# ST_LINK_V2-1.net
KiCad netlist of a schematic drawn in Altium Designer
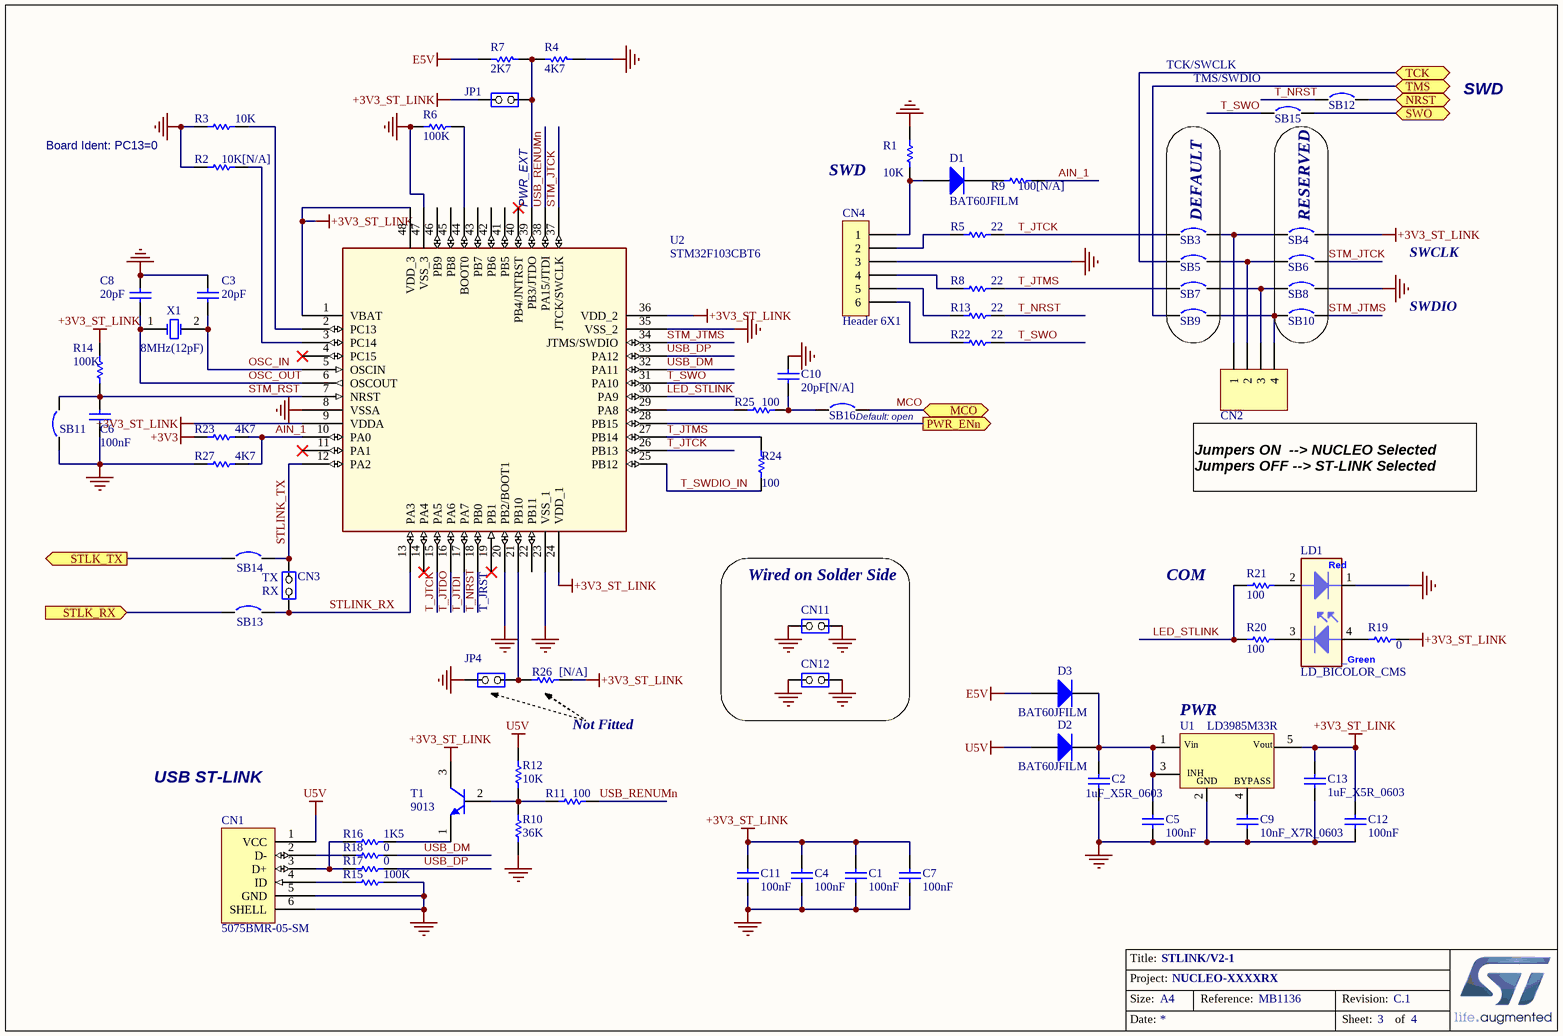
[diagram p0: ST_LINK_V2-1.SCHDOC]

(export (version "E")
  (design (tool "Eeschema 10.0.6"))
  (components
    (comp (ref "C1")
      (value "100nF")
      (footprint "0603C")
      (description "Capacitor 0402 / 0603 / 0805")
      (libsource (lib "MCD_TOOLS") (part "Capacitor_ST"))
    )
    (comp (ref "C2")
      (value "1uF_X5R_0603")
      (footprint "0603C")
      (description "0603  X5R 1µF")
      (fields (field (name "TOLERANCE") "10%"))
      (libsource (lib "MB963_1") (part "CAP SMD 0603  X5R 1µF 25V 10%"))
    )
    (comp (ref "C3")
      (value "20pF")
      (footprint "0603C")
      (description "Capacitor 0402 / 0603 / 0805")
      (libsource (lib "MCD_TOOLS") (part "Capacitor_ST"))
    )
    (comp (ref "C4")
      (value "100nF")
      (footprint "0603C")
      (description "Capacitor 0402 / 0603 / 0805")
      (libsource (lib "MCD_TOOLS") (part "Capacitor_ST"))
    )
    (comp (ref "C5")
      (value "100nF")
      (footprint "0603C")
      (description "Capacitor 0402 / 0603 / 0805")
      (libsource (lib "MCD_TOOLS") (part "Capacitor_ST"))
    )
    (comp (ref "C6")
      (value "100nF")
      (footprint "0603C")
      (description "Capacitor 0402 / 0603 / 0805")
      (libsource (lib "MCD_TOOLS") (part "Capacitor_ST"))
    )
    (comp (ref "C7")
      (value "100nF")
      (footprint "0603C")
      (description "Capacitor 0402 / 0603 / 0805")
      (libsource (lib "MCD_TOOLS") (part "Capacitor_ST"))
    )
    (comp (ref "C8")
      (value "20pF")
      (footprint "0603C")
      (description "Capacitor 0402 / 0603 / 0805")
      (libsource (lib "MCD_TOOLS") (part "Capacitor_ST"))
    )
    (comp (ref "C9")
      (value "10nF_X7R_0603")
      (footprint "0603C")
      (description "0603  X7R 10NF")
      (fields (field (name "TOLERANCE") "10%"))
      (libsource (lib "MB963_1") (part "CAP SMD 0603  X7R 10000PF 50V 10%"))
    )
    (comp (ref "C10")
      (value "20pF[N/A]")
      (footprint "0603C")
      (description "Capacitor 0402 / 0603 / 0805")
      (libsource (lib "MCD_TOOLS") (part "Capacitor_ST"))
    )
    (comp (ref "C11")
      (value "100nF")
      (footprint "0603C")
      (description "Capacitor 0402 / 0603 / 0805")
      (libsource (lib "MCD_TOOLS") (part "Capacitor_ST"))
    )
    (comp (ref "C12")
      (value "100nF")
      (footprint "0603C")
      (description "Capacitor 0402 / 0603 / 0805")
      (libsource (lib "MCD_TOOLS") (part "Capacitor_ST"))
    )
    (comp (ref "C13")
      (value "1uF_X5R_0603")
      (footprint "0603C")
      (description "0603  X5R 1µF")
      (fields (field (name "TOLERANCE") "10%"))
      (libsource (lib "MB963_1") (part "CAP SMD 0603  X5R 1µF 25V 10%"))
    )
    (comp (ref "CN1")
      (value "5075BMR-05-SM")
      (footprint "USB-MINI-B-SMD")
      (description "USB-MINI-typeB connector")
      (libsource (lib "MCD_TOOLS") (part "USB-MINI-typeB connector"))
    )
    (comp (ref "CN2")
      (value "Header 4")
      (footprint "1*4")
      (description "Header, 4-Pin, Single row")
      (fields (field (name "PUBLISHER") "Altium Limited"))
      (libsource (lib "Nucleo_64") (part "Header 4"))
    )
    (comp (ref "CN3") (value "~") (footprint "SIP2/2.54") (libsource (lib "MCD_TOOLS") (part "JP2")))
    (comp (ref "CN4")
      (value "Header 6X1")
      (footprint "1*6P")
      (description "Header, 6-Pin, Single row")
      (fields (field (name "PUBLISHER") "Altium Limited"))
      (libsource (lib "Nucleo_64") (part "Header 6X1"))
    )
    (comp (ref "CN11") (value "~") (footprint "SIP2/2.54") (libsource (lib "*") (part "JP2")))
    (comp (ref "CN12") (value "~") (footprint "SIP2/2.54") (libsource (lib "*") (part "JP2")))
    (comp (ref "D1")
      (value "BAT60JFILM")
      (footprint "SOD323/A")
      (libsource (lib "MCD_TOOLS") (part "BAT60JFILM"))
    )
    (comp (ref "D2")
      (value "BAT60JFILM")
      (footprint "SOD323/A")
      (libsource (lib "MCD_TOOLS") (part "BAT60JFILM"))
    )
    (comp (ref "D3")
      (value "BAT60JFILM")
      (footprint "SOD323/A")
      (libsource (lib "MCD_TOOLS") (part "BAT60JFILM"))
    )
    (comp (ref "JP1") (value "~") (footprint "SIP2/2.54") (libsource (lib "*") (part "JP2")))
    (comp (ref "JP4") (value "~") (footprint "SIP2/2.54") (libsource (lib "*") (part "JP2")))
    (comp (ref "LD1")
      (value "LD_BICOLOR_CMS")
      (footprint "HSMF-A201")
      (description "Bicolor Led")
      (libsource (lib "MCD_TOOLS") (part "LD_BICOLOR_CMS"))
    )
    (comp (ref "R1")
      (value "10K")
      (footprint "0603R")
      (description "Resistor 0402 or 0603 or 0805")
      (libsource (lib "Miscellaneous Devices") (part "Res1"))
    )
    (comp (ref "R2")
      (value "10K[N/A]")
      (footprint "0603R")
      (description "Resistor 0402 or 0603 or 0805")
      (libsource (lib "Miscellaneous Devices") (part "Res1"))
    )
    (comp (ref "R3")
      (value "10K")
      (footprint "0603R")
      (description "Resistor 0402 or 0603 or 0805")
      (libsource (lib "Miscellaneous Devices") (part "Res1"))
    )
    (comp (ref "R4")
      (value "4K7")
      (footprint "0603R")
      (description "Resistor")
      (fields (field (name "PUBLISHER") "Altium Limited"))
      (libsource (lib "") (part "Res1_1"))
    )
    (comp (ref "R5")
      (value "22")
      (footprint "0603R")
      (description "Resistor 0402 or 0603 or 0805")
      (libsource (lib "Miscellaneous Devices") (part "Res1"))
    )
    (comp (ref "R6")
      (value "100K")
      (footprint "0603R")
      (description "Resistor 0402 or 0603 or 0805")
      (libsource (lib "Miscellaneous Devices") (part "Res1"))
    )
    (comp (ref "R7")
      (value "2K7")
      (footprint "0603R")
      (description "Resistor")
      (fields (field (name "PUBLISHER") "Altium Limited"))
      (libsource (lib "") (part "Res1_1"))
    )
    (comp (ref "R8")
      (value "22")
      (footprint "0603R")
      (description "Resistor 0402 or 0603 or 0805")
      (libsource (lib "Miscellaneous Devices") (part "Res1"))
    )
    (comp (ref "R9")
      (value "100[N/A]")
      (footprint "0603R")
      (description "Resistor 0402 or 0603 or 0805")
      (libsource (lib "Miscellaneous Devices") (part "Res1"))
    )
    (comp (ref "R10")
      (value "36K")
      (footprint "0603R")
      (description "Resistor")
      (fields (field (name "PUBLISHER") "Altium Limited"))
      (libsource (lib "") (part "Res1_2"))
    )
    (comp (ref "R11")
      (value "100")
      (footprint "0603R")
      (description "Resistor 0402 or 0603 or 0805")
      (libsource (lib "Miscellaneous Devices") (part "Res1"))
    )
    (comp (ref "R12")
      (value "10K")
      (footprint "0603R")
      (description "Resistor")
      (fields (field (name "PUBLISHER") "Altium Limited"))
      (libsource (lib "") (part "Res1_2"))
    )
    (comp (ref "R13")
      (value "22")
      (footprint "0603R")
      (description "Resistor 0402 or 0603 or 0805")
      (libsource (lib "Miscellaneous Devices") (part "Res1"))
    )
    (comp (ref "R14")
      (value "100K")
      (footprint "0603R")
      (description "Resistor 0402 or 0603 or 0805")
      (libsource (lib "Miscellaneous Devices") (part "Res1"))
    )
    (comp (ref "R15")
      (value "100K")
      (footprint "0603R")
      (description "Resistor 0402 or 0603 or 0805")
      (libsource (lib "Miscellaneous Devices") (part "Res1"))
    )
    (comp (ref "R16")
      (value "1K5")
      (footprint "0603R")
      (description "Resistor 0402 or 0603 or 0805")
      (libsource (lib "Miscellaneous Devices") (part "Res1"))
    )
    (comp (ref "R17")
      (value "0")
      (footprint "0603R")
      (description "Resistor 0402 or 0603 or 0805")
      (libsource (lib "Miscellaneous Devices") (part "Res1"))
    )
    (comp (ref "R18")
      (value "0")
      (footprint "0603R")
      (description "Resistor 0402 or 0603 or 0805")
      (libsource (lib "Miscellaneous Devices") (part "Res1"))
    )
    (comp (ref "R19")
      (value "0")
      (footprint "0603R")
      (description "Resistor 0402 or 0603 or 0805")
      (libsource (lib "Miscellaneous Devices") (part "Res1"))
    )
    (comp (ref "R20")
      (value "100")
      (footprint "0603R")
      (description "Resistor 0402 or 0603 or 0805")
      (libsource (lib "Miscellaneous Devices") (part "Res1"))
    )
    (comp (ref "R21")
      (value "100")
      (footprint "0603R")
      (description "Resistor 0402 or 0603 or 0805")
      (libsource (lib "Miscellaneous Devices") (part "Res1"))
    )
    (comp (ref "R22")
      (value "22")
      (footprint "0603R")
      (description "Resistor 0402 or 0603 or 0805")
      (libsource (lib "Miscellaneous Devices") (part "Res1"))
    )
    (comp (ref "R23")
      (value "4K7")
      (footprint "0603R")
      (description "Resistor 0402 or 0603 or 0805")
      (libsource (lib "Miscellaneous Devices") (part "Res1"))
    )
    (comp (ref "R24")
      (value "100")
      (footprint "0603R")
      (description "Resistor 0402 or 0603 or 0805")
      (libsource (lib "Miscellaneous Devices") (part "Res1"))
    )
    (comp (ref "R25")
      (value "100")
      (footprint "0603R")
      (description "Resistor 0402 or 0603 or 0805")
      (libsource (lib "Miscellaneous Devices") (part "Res1"))
    )
    (comp (ref "R26")
      (value "[N/A]")
      (footprint "0603R")
      (description "Resistor")
      (fields (field (name "PUBLISHER") "Altium Limited"))
      (libsource (lib "") (part "Res1_2"))
    )
    (comp (ref "R27")
      (value "4K7")
      (footprint "0603R")
      (description "Resistor 0402 or 0603 or 0805")
      (libsource (lib "Miscellaneous Devices") (part "Res1"))
    )
    (comp (ref "SB3")
      (value "Circuit Breaker")
      (footprint "JP2_SMD")
      (fields (field (name "PUBLISHER") "Altium Limited"))
      (libsource (lib "MB915") (part "Circuit Breaker"))
    )
    (comp (ref "SB4")
      (value "Circuit Breaker")
      (footprint "JP2_SMD")
      (fields (field (name "PUBLISHER") "Altium Limited"))
      (libsource (lib "MB915") (part "Circuit Breaker"))
    )
    (comp (ref "SB5")
      (value "Circuit Breaker")
      (footprint "JP2_SMD")
      (fields (field (name "PUBLISHER") "Altium Limited"))
      (libsource (lib "MB915") (part "Circuit Breaker"))
    )
    (comp (ref "SB6")
      (value "Circuit Breaker")
      (footprint "JP2_SMD")
      (fields (field (name "PUBLISHER") "Altium Limited"))
      (libsource (lib "MB915") (part "Circuit Breaker"))
    )
    (comp (ref "SB7")
      (value "Circuit Breaker")
      (footprint "JP2_SMD")
      (fields (field (name "PUBLISHER") "Altium Limited"))
      (libsource (lib "MB915") (part "Circuit Breaker"))
    )
    (comp (ref "SB8")
      (value "Circuit Breaker")
      (footprint "JP2_SMD")
      (fields (field (name "PUBLISHER") "Altium Limited"))
      (libsource (lib "MB915") (part "Circuit Breaker"))
    )
    (comp (ref "SB9")
      (value "Circuit Breaker")
      (footprint "JP2_SMD")
      (fields (field (name "PUBLISHER") "Altium Limited"))
      (libsource (lib "MB915") (part "Circuit Breaker"))
    )
    (comp (ref "SB10")
      (value "Circuit Breaker")
      (footprint "JP2_SMD")
      (fields (field (name "PUBLISHER") "Altium Limited"))
      (libsource (lib "MB915") (part "Circuit Breaker"))
    )
    (comp (ref "SB11")
      (value "Circuit Breaker")
      (footprint "JP2_SMD")
      (fields (field (name "PUBLISHER") "Altium Limited"))
      (libsource (lib "MB915") (part "Circuit Breaker"))
    )
    (comp (ref "SB12")
      (value "Circuit Breaker")
      (footprint "JP2_SMD")
      (fields (field (name "PUBLISHER") "Altium Limited"))
      (libsource (lib "MB915") (part "Circuit Breaker"))
    )
    (comp (ref "SB13")
      (value "Circuit Breaker")
      (footprint "JP2_SMD")
      (fields (field (name "PUBLISHER") "Altium Limited"))
      (libsource (lib "MCD_TOOLS") (part "Circuit Breaker"))
    )
    (comp (ref "SB14")
      (value "Circuit Breaker")
      (footprint "JP2_SMD")
      (fields (field (name "PUBLISHER") "Altium Limited"))
      (libsource (lib "MCD_TOOLS") (part "Circuit Breaker"))
    )
    (comp (ref "SB15")
      (value "Circuit Breaker")
      (footprint "JP2_SMD")
      (fields (field (name "PUBLISHER") "Altium Limited"))
      (libsource (lib "MCD_TOOLS") (part "Circuit Breaker"))
    )
    (comp (ref "SB16")
      (value "Circuit Breaker")
      (footprint "JP2_SMD")
      (fields (field (name "PUBLISHER") "Altium Limited"))
      (libsource (lib "MCD_TOOLS") (part "Circuit Breaker"))
    )
    (comp (ref "T1")
      (value "9013")
      (footprint "SOT-23")
      (description "NPN Bipolar Transistor")
      (fields (field (name "PUBLISHER") "Altium Limited"))
      (libsource (lib "Miscellaneous Devices") (part "NPN"))
    )
    (comp (ref "U1")
      (value "LD3985M33R")
      (footprint "SOT-23-5L")
      (description "Ultra low drop-low noise BiCMOS voltage, regulators low ESR capacitors compatible")
      (libsource (lib "MCD_TOOLS") (part "LD3985M33R"))
    )
    (comp (ref "U2")
      (value "STM32F103CBT6")
      (footprint "QFP48 7X7")
      (description "Medium-density performance line ARM-based 32-bit MCU with 64KB Flash")
      (libsource (lib "Nucleo_64") (part "STM32F103CBT6"))
    )
    (comp (ref "X1")
      (value "8MHz(12pF)")
      (footprint "XTAL1")
      (description "Crystal Oscillator")
      (fields (field (name "PUBLISHER") "Altium Limited"))
      (libsource (lib "MB963_1") (part "XTAL"))
    )
  )
  (nets
    (net (code "1") (name "+3V3") (class "Default")
      (node (ref "R23") (pin "1") (pinfunction "1_1") (pintype "passive"))
    )
    (net (code "2") (name "+3V3_ST_LINK") (class "Default")
      (node (ref "C1") (pin "2") (pinfunction "2_2") (pintype "passive"))
      (node (ref "C11") (pin "2") (pinfunction "2_2") (pintype "passive"))
      (node (ref "C12") (pin "2") (pinfunction "2_2") (pintype "passive"))
      (node (ref "C13") (pin "1") (pinfunction "1_1") (pintype "passive"))
      (node (ref "C4") (pin "2") (pinfunction "2_2") (pintype "passive"))
      (node (ref "C7") (pin "2") (pinfunction "2_2") (pintype "passive"))
      (node (ref "JP1") (pin "1") (pinfunction "COMMON_1") (pintype "passive"))
      (node (ref "R14") (pin "2") (pinfunction "2_2") (pintype "passive"))
      (node (ref "R19") (pin "2") (pinfunction "2_2") (pintype "passive"))
      (node (ref "R26") (pin "1") (pinfunction "1_1") (pintype "passive"))
      (node (ref "SB4") (pin "2") (pinfunction "2_2") (pintype "passive"))
      (node (ref "T1") (pin "3") (pinfunction "C_3") (pintype "passive"))
      (node (ref "U1") (pin "5") (pinfunction "Vout_5") (pintype "passive"))
      (node (ref "U2") (pin "1") (pinfunction "VBAT_1") (pintype "power_in"))
      (node (ref "U2") (pin "24") (pinfunction "VDD_1_24") (pintype "power_in"))
      (node (ref "U2") (pin "36") (pinfunction "VDD_2_36") (pintype "power_in"))
      (node (ref "U2") (pin "48") (pinfunction "VDD_3_48") (pintype "power_in"))
      (node (ref "U2") (pin "9") (pinfunction "VDDA_9") (pintype "power_in"))
    )
    (net (code "3") (name "/AIN_1") (class "Default")
      (node (ref "R23") (pin "2") (pinfunction "2_2") (pintype "passive"))
      (node (ref "R27") (pin "2") (pinfunction "2_2") (pintype "passive"))
      (node (ref "R9") (pin "2") (pinfunction "2_2") (pintype "passive"))
      (node (ref "U2") (pin "10") (pinfunction "PA0_10") (pintype "bidirectional"))
    )
    (net (code "4") (name "/LED_STLINK") (class "Default")
      (node (ref "R20") (pin "1") (pinfunction "1_1") (pintype "passive"))
      (node (ref "R21") (pin "1") (pinfunction "1_1") (pintype "passive"))
      (node (ref "U2") (pin "30") (pinfunction "PA9_30") (pintype "bidirectional"))
    )
    (net (code "5") (name "/MCO") (class "Default")
      (node (ref "SB16") (pin "2") (pinfunction "2_2") (pintype "passive"))
    )
    (net (code "6") (name "/NRST") (class "Default")
      (node (ref "SB12") (pin "2") (pinfunction "2_2") (pintype "passive"))
    )
    (net (code "7") (name "/OSC_IN") (class "Default")
      (node (ref "C3") (pin "1") (pinfunction "1_1") (pintype "passive"))
      (node (ref "U2") (pin "5") (pinfunction "OSCIN_5") (pintype "input"))
      (node (ref "X1") (pin "2") (pinfunction "OSC2_2") (pintype "passive"))
    )
    (net (code "8") (name "/OSC_OUT") (class "Default")
      (node (ref "C8") (pin "1") (pinfunction "1_1") (pintype "passive"))
      (node (ref "U2") (pin "6") (pinfunction "OSCOUT_6") (pintype "output"))
      (node (ref "X1") (pin "1") (pinfunction "OSC1_1") (pintype "passive"))
    )
    (net (code "9") (name "/PWR_ENn") (class "Default")
      (node (ref "U2") (pin "28") (pinfunction "PB15_28") (pintype "bidirectional"))
    )
    (net (code "10") (name "/STLINK_RX") (class "Default")
      (node (ref "CN3") (pin "1") (pinfunction "COMMON_1") (pintype "passive"))
      (node (ref "SB13") (pin "2") (pinfunction "2_2") (pintype "passive"))
      (node (ref "U2") (pin "13") (pinfunction "PA3_13") (pintype "bidirectional"))
    )
    (net (code "11") (name "/STLINK_TX") (class "Default")
      (node (ref "CN3") (pin "2") (pinfunction "NO_2") (pintype "passive"))
      (node (ref "SB14") (pin "2") (pinfunction "2_2") (pintype "passive"))
      (node (ref "U2") (pin "12") (pinfunction "PA2_12") (pintype "bidirectional"))
    )
    (net (code "12") (name "/STLK_RX") (class "Default")
      (node (ref "SB13") (pin "1") (pinfunction "1_1") (pintype "passive"))
    )
    (net (code "13") (name "/STLK_TX") (class "Default")
      (node (ref "SB14") (pin "1") (pinfunction "1_1") (pintype "passive"))
    )
    (net (code "14") (name "/STM_JTCK") (class "Default")
      (node (ref "SB6") (pin "2") (pinfunction "2_2") (pintype "passive"))
      (node (ref "U2") (pin "37") (pinfunction "JTCK/SWCLK_37") (pintype "bidirectional"))
    )
    (net (code "15") (name "/STM_JTMS") (class "Default")
      (node (ref "SB10") (pin "2") (pinfunction "2_2") (pintype "passive"))
      (node (ref "U2") (pin "34") (pinfunction "JTMS/SWDIO_34") (pintype "bidirectional"))
    )
    (net (code "16") (name "/STM_RST") (class "Default")
      (node (ref "C6") (pin "2") (pinfunction "2_2") (pintype "passive"))
      (node (ref "R14") (pin "1") (pinfunction "1_1") (pintype "passive"))
      (node (ref "SB11") (pin "2") (pinfunction "2_2") (pintype "passive"))
      (node (ref "U2") (pin "7") (pinfunction "NRST_7") (pintype "input"))
    )
    (net (code "17") (name "/SWO") (class "Default")
      (node (ref "SB15") (pin "2") (pinfunction "2_2") (pintype "passive"))
    )
    (net (code "18") (name "/TCK") (class "Default")
      (node (ref "SB5") (pin "1") (pinfunction "1_1") (pintype "passive"))
    )
    (net (code "19") (name "/TMS") (class "Default")
      (node (ref "SB9") (pin "1") (pinfunction "1_1") (pintype "passive"))
    )
    (net (code "20") (name "/T_JTCK") (class "Default")
      (node (ref "R5") (pin "2") (pinfunction "2_2") (pintype "passive"))
      (node (ref "SB3") (pin "1") (pinfunction "1_1") (pintype "passive"))
      (node (ref "U2") (pin "15") (pinfunction "PA5_15") (pintype "bidirectional"))
      (node (ref "U2") (pin "26") (pinfunction "PB13_26") (pintype "bidirectional"))
    )
    (net (code "21") (name "/T_JTDI") (class "Default")
      (node (ref "U2") (pin "17") (pinfunction "PA7_17") (pintype "bidirectional"))
    )
    (net (code "22") (name "/T_JTDO") (class "Default")
      (node (ref "U2") (pin "16") (pinfunction "PA6_16") (pintype "bidirectional"))
    )
    (net (code "23") (name "/T_JTMS") (class "Default")
      (node (ref "R24") (pin "2") (pinfunction "2_2") (pintype "passive"))
      (node (ref "R8") (pin "2") (pinfunction "2_2") (pintype "passive"))
      (node (ref "SB7") (pin "1") (pinfunction "1_1") (pintype "passive"))
      (node (ref "U2") (pin "27") (pinfunction "PB14_27") (pintype "bidirectional"))
    )
    (net (code "24") (name "/T_NRST") (class "Default")
      (node (ref "R13") (pin "2") (pinfunction "2_2") (pintype "passive"))
      (node (ref "SB12") (pin "1") (pinfunction "1_1") (pintype "passive"))
      (node (ref "U2") (pin "18") (pinfunction "PB0_18") (pintype "bidirectional"))
    )
    (net (code "25") (name "/T_SWDIO_IN") (class "Default")
      (node (ref "R24") (pin "1") (pinfunction "1_1") (pintype "passive"))
      (node (ref "U2") (pin "25") (pinfunction "PB12_25") (pintype "bidirectional"))
    )
    (net (code "26") (name "/T_SWO") (class "Default")
      (node (ref "R22") (pin "2") (pinfunction "2_2") (pintype "passive"))
      (node (ref "SB15") (pin "1") (pinfunction "1_1") (pintype "passive"))
      (node (ref "U2") (pin "31") (pinfunction "PA10_31") (pintype "bidirectional"))
    )
    (net (code "27") (name "/USB_DM") (class "Default")
      (node (ref "R18") (pin "2") (pinfunction "2_2") (pintype "passive"))
      (node (ref "U2") (pin "32") (pinfunction "PA11_32") (pintype "bidirectional"))
    )
    (net (code "28") (name "/USB_DP") (class "Default")
      (node (ref "R17") (pin "2") (pinfunction "2_2") (pintype "passive"))
      (node (ref "U2") (pin "33") (pinfunction "PA12_33") (pintype "bidirectional"))
    )
    (net (code "29") (name "/USB_RENUMn") (class "Default")
      (node (ref "R11") (pin "2") (pinfunction "2_2") (pintype "passive"))
      (node (ref "U2") (pin "38") (pinfunction "PA15/JTDI_38") (pintype "bidirectional"))
    )
    (net (code "30") (name "E5V") (class "Default")
      (node (ref "D3") (pin "1") (pinfunction "A_1") (pintype "passive"))
      (node (ref "R7") (pin "1") (pinfunction "1_1") (pintype "passive"))
    )
    (net (code "31") (name "GND") (class "Default")
      (node (ref "C1") (pin "1") (pinfunction "1_1") (pintype "passive"))
      (node (ref "C10") (pin "2") (pinfunction "2_2") (pintype "passive"))
      (node (ref "C11") (pin "1") (pinfunction "1_1") (pintype "passive"))
      (node (ref "C12") (pin "1") (pinfunction "1_1") (pintype "passive"))
      (node (ref "C13") (pin "2") (pinfunction "2_2") (pintype "passive"))
      (node (ref "C2") (pin "1") (pinfunction "1_1") (pintype "passive"))
      (node (ref "C3") (pin "2") (pinfunction "2_2") (pintype "passive"))
      (node (ref "C4") (pin "1") (pinfunction "1_1") (pintype "passive"))
      (node (ref "C5") (pin "1") (pinfunction "1_1") (pintype "passive"))
      (node (ref "C6") (pin "1") (pinfunction "1_1") (pintype "passive"))
      (node (ref "C7") (pin "1") (pinfunction "1_1") (pintype "passive"))
      (node (ref "C8") (pin "2") (pinfunction "2_2") (pintype "passive"))
      (node (ref "C9") (pin "1") (pinfunction "1_1") (pintype "passive"))
      (node (ref "CN1") (pin "5") (pinfunction "GND_5") (pintype "power_in"))
      (node (ref "CN1") (pin "6") (pinfunction "SHELL_6") (pintype "power_in"))
      (node (ref "CN11") (pin "1") (pinfunction "COMMON_1") (pintype "passive"))
      (node (ref "CN11") (pin "2") (pinfunction "NO_2") (pintype "passive"))
      (node (ref "CN12") (pin "1") (pinfunction "COMMON_1") (pintype "passive"))
      (node (ref "CN12") (pin "2") (pinfunction "NO_2") (pintype "passive"))
      (node (ref "CN4") (pin "3") (pinfunction "3_3") (pintype "passive"))
      (node (ref "JP4") (pin "1") (pinfunction "COMMON_1") (pintype "passive"))
      (node (ref "LD1") (pin "1") (pinfunction "1_1") (pintype "passive"))
      (node (ref "R1") (pin "2") (pinfunction "2_2") (pintype "passive"))
      (node (ref "R10") (pin "1") (pinfunction "1_1") (pintype "passive"))
      (node (ref "R15") (pin "2") (pinfunction "2_2") (pintype "passive"))
      (node (ref "R2") (pin "1") (pinfunction "1_1") (pintype "passive"))
      (node (ref "R27") (pin "1") (pinfunction "1_1") (pintype "passive"))
      (node (ref "R3") (pin "1") (pinfunction "1_1") (pintype "passive"))
      (node (ref "R4") (pin "2") (pinfunction "2_2") (pintype "passive"))
      (node (ref "R6") (pin "1") (pinfunction "1_1") (pintype "passive"))
      (node (ref "SB11") (pin "1") (pinfunction "1_1") (pintype "passive"))
      (node (ref "SB8") (pin "2") (pinfunction "2_2") (pintype "passive"))
      (node (ref "U1") (pin "2") (pinfunction "GND_2") (pintype "passive"))
      (node (ref "U2") (pin "20") (pinfunction "PB2/BOOT1_20") (pintype "bidirectional"))
      (node (ref "U2") (pin "23") (pinfunction "VSS_1_23") (pintype "power_in"))
      (node (ref "U2") (pin "35") (pinfunction "VSS_2_35") (pintype "power_in"))
      (node (ref "U2") (pin "47") (pinfunction "VSS_3_47") (pintype "power_in"))
      (node (ref "U2") (pin "8") (pinfunction "VSSA_8") (pintype "power_in"))
    )
    (net (code "32") (name "Net-(C10-Pad1)") (class "Default")
      (node (ref "C10") (pin "1") (pinfunction "1_1") (pintype "passive"))
      (node (ref "R25") (pin "2") (pinfunction "2_2") (pintype "passive"))
      (node (ref "SB16") (pin "1") (pinfunction "1_1") (pintype "passive"))
    )
    (net (code "33") (name "Net-(CN1-D+)") (class "Default")
      (node (ref "CN1") (pin "3") (pinfunction "D+_3") (pintype "bidirectional"))
      (node (ref "R16") (pin "1") (pinfunction "1_1") (pintype "passive"))
      (node (ref "R17") (pin "1") (pinfunction "1_1") (pintype "passive"))
    )
    (net (code "34") (name "Net-(CN1-D-)") (class "Default")
      (node (ref "CN1") (pin "2") (pinfunction "D-_2") (pintype "bidirectional"))
      (node (ref "R18") (pin "1") (pinfunction "1_1") (pintype "passive"))
    )
    (net (code "35") (name "Net-(CN1-ID)") (class "Default")
      (node (ref "CN1") (pin "4") (pinfunction "ID_4") (pintype "input"))
      (node (ref "R15") (pin "1") (pinfunction "1_1") (pintype "passive"))
    )
    (net (code "36") (name "Net-(CN2-Pad1)") (class "Default")
      (node (ref "CN2") (pin "1") (pinfunction "1_1") (pintype "passive"))
      (node (ref "SB3") (pin "2") (pinfunction "2_2") (pintype "passive"))
      (node (ref "SB4") (pin "1") (pinfunction "1_1") (pintype "passive"))
    )
    (net (code "37") (name "Net-(CN2-Pad2)") (class "Default")
      (node (ref "CN2") (pin "2") (pinfunction "2_2") (pintype "passive"))
      (node (ref "SB5") (pin "2") (pinfunction "2_2") (pintype "passive"))
      (node (ref "SB6") (pin "1") (pinfunction "1_1") (pintype "passive"))
    )
    (net (code "38") (name "Net-(CN2-Pad3)") (class "Default")
      (node (ref "CN2") (pin "3") (pinfunction "3_3") (pintype "passive"))
      (node (ref "SB7") (pin "2") (pinfunction "2_2") (pintype "passive"))
      (node (ref "SB8") (pin "1") (pinfunction "1_1") (pintype "passive"))
    )
    (net (code "39") (name "Net-(CN2-Pad4)") (class "Default")
      (node (ref "CN2") (pin "4") (pinfunction "4_4") (pintype "passive"))
      (node (ref "SB10") (pin "1") (pinfunction "1_1") (pintype "passive"))
      (node (ref "SB9") (pin "2") (pinfunction "2_2") (pintype "passive"))
    )
    (net (code "40") (name "Net-(CN4-Pad2)") (class "Default")
      (node (ref "CN4") (pin "2") (pinfunction "2_2") (pintype "passive"))
      (node (ref "R5") (pin "1") (pinfunction "1_1") (pintype "passive"))
    )
    (net (code "41") (name "Net-(CN4-Pad4)") (class "Default")
      (node (ref "CN4") (pin "4") (pinfunction "4_4") (pintype "passive"))
      (node (ref "R8") (pin "1") (pinfunction "1_1") (pintype "passive"))
    )
    (net (code "42") (name "Net-(CN4-Pad5)") (class "Default")
      (node (ref "CN4") (pin "5") (pinfunction "5_5") (pintype "passive"))
      (node (ref "R13") (pin "1") (pinfunction "1_1") (pintype "passive"))
    )
    (net (code "43") (name "Net-(CN4-Pad6)") (class "Default")
      (node (ref "CN4") (pin "6") (pinfunction "6_6") (pintype "passive"))
      (node (ref "R22") (pin "1") (pinfunction "1_1") (pintype "passive"))
    )
    (net (code "44") (name "Net-(D1-A)") (class "Default")
      (node (ref "CN4") (pin "1") (pinfunction "1_1") (pintype "passive"))
      (node (ref "D1") (pin "1") (pinfunction "A_1") (pintype "passive"))
      (node (ref "R1") (pin "1") (pinfunction "1_1") (pintype "passive"))
    )
    (net (code "45") (name "Net-(D1-K)") (class "Default")
      (node (ref "D1") (pin "2") (pinfunction "K_2") (pintype "passive"))
      (node (ref "R9") (pin "1") (pinfunction "1_1") (pintype "passive"))
    )
    (net (code "46") (name "Net-(D2-K)") (class "Default")
      (node (ref "C2") (pin "2") (pinfunction "2_2") (pintype "passive"))
      (node (ref "C5") (pin "2") (pinfunction "2_2") (pintype "passive"))
      (node (ref "D2") (pin "2") (pinfunction "K_2") (pintype "passive"))
      (node (ref "D3") (pin "2") (pinfunction "K_2") (pintype "passive"))
      (node (ref "U1") (pin "1") (pinfunction "Vin_1") (pintype "passive"))
      (node (ref "U1") (pin "3") (pinfunction "CE_3") (pintype "passive"))
    )
    (net (code "47") (name "Net-(JP1-NO)") (class "Default")
      (node (ref "JP1") (pin "2") (pinfunction "NO_2") (pintype "passive"))
      (node (ref "R4") (pin "1") (pinfunction "1_1") (pintype "passive"))
      (node (ref "R7") (pin "2") (pinfunction "2_2") (pintype "passive"))
      (node (ref "U2") (pin "39") (pinfunction "PB3/JTDO_39") (pintype "bidirectional"))
    )
    (net (code "48") (name "Net-(JP4-NO)") (class "Default")
      (node (ref "JP4") (pin "2") (pinfunction "NO_2") (pintype "passive"))
      (node (ref "R26") (pin "2") (pinfunction "2_2") (pintype "passive"))
      (node (ref "U2") (pin "21") (pinfunction "PB10_21") (pintype "bidirectional"))
    )
    (net (code "49") (name "Net-(LD1-Pad2)") (class "Default")
      (node (ref "LD1") (pin "2") (pinfunction "2_2") (pintype "passive"))
      (node (ref "R21") (pin "2") (pinfunction "2_2") (pintype "passive"))
    )
    (net (code "50") (name "Net-(LD1-Pad3)") (class "Default")
      (node (ref "LD1") (pin "3") (pinfunction "3_3") (pintype "passive"))
      (node (ref "R20") (pin "2") (pinfunction "2_2") (pintype "passive"))
    )
    (net (code "51") (name "Net-(LD1-Pad4)") (class "Default")
      (node (ref "LD1") (pin "4") (pinfunction "4_4") (pintype "passive"))
      (node (ref "R19") (pin "1") (pinfunction "1_1") (pintype "passive"))
    )
    (net (code "52") (name "Net-(T1-B)") (class "Default")
      (node (ref "R10") (pin "2") (pinfunction "2_2") (pintype "passive"))
      (node (ref "R11") (pin "1") (pinfunction "1_1") (pintype "passive"))
      (node (ref "R12") (pin "1") (pinfunction "1_1") (pintype "passive"))
      (node (ref "T1") (pin "2") (pinfunction "B_2") (pintype "passive"))
    )
    (net (code "53") (name "Net-(T1-E)") (class "Default")
      (node (ref "R16") (pin "2") (pinfunction "2_2") (pintype "passive"))
      (node (ref "T1") (pin "1") (pinfunction "E_1") (pintype "passive"))
    )
    (net (code "54") (name "Net-(U1-BYPASS)") (class "Default")
      (node (ref "C9") (pin "2") (pinfunction "2_2") (pintype "passive"))
      (node (ref "U1") (pin "4") (pinfunction "BYPASS_4") (pintype "passive"))
    )
    (net (code "55") (name "Net-(U2-BOOT0)") (class "Default")
      (node (ref "R6") (pin "2") (pinfunction "2_2") (pintype "passive"))
      (node (ref "U2") (pin "44") (pinfunction "BOOT0_44") (pintype "bidirectional"))
    )
    (net (code "56") (name "Net-(U2-PA8)") (class "Default")
      (node (ref "R25") (pin "1") (pinfunction "1_1") (pintype "passive"))
      (node (ref "U2") (pin "29") (pinfunction "PA8_29") (pintype "bidirectional"))
    )
    (net (code "57") (name "Net-(U2-PC13)") (class "Default")
      (node (ref "R3") (pin "2") (pinfunction "2_2") (pintype "passive"))
      (node (ref "U2") (pin "2") (pinfunction "PC13_2") (pintype "bidirectional"))
    )
    (net (code "58") (name "Net-(U2-PC14)") (class "Default")
      (node (ref "R2") (pin "2") (pinfunction "2_2") (pintype "passive"))
      (node (ref "U2") (pin "3") (pinfunction "PC14_3") (pintype "bidirectional"))
    )
    (net (code "59") (name "U5V") (class "Default")
      (node (ref "CN1") (pin "1") (pinfunction "VCC_1") (pintype "power_in"))
      (node (ref "D2") (pin "1") (pinfunction "A_1") (pintype "passive"))
      (node (ref "R12") (pin "2") (pinfunction "2_2") (pintype "passive"))
    )
    (net (code "60") (name "unconnected-(U2-PA1-Pad11)") (class "Default")
      (node (ref "U2") (pin "11") (pinfunction "PA1_11") (pintype "bidirectional+no_connect"))
    )
    (net (code "61") (name "unconnected-(U2-PA4-Pad14)") (class "Default")
      (node (ref "U2") (pin "14") (pinfunction "PA4_14") (pintype "bidirectional+no_connect"))
    )
    (net (code "62") (name "unconnected-(U2-PB1-Pad19)") (class "Default")
      (node (ref "U2") (pin "19") (pinfunction "PB1_19") (pintype "input+no_connect"))
    )
    (net (code "63") (name "unconnected-(U2-PB4{slash}JNTRST-Pad40)") (class "Default")
      (node (ref "U2") (pin "40") (pinfunction "PB4/JNTRST_40") (pintype "bidirectional+no_connect"))
    )
    (net (code "64") (name "unconnected-(U2-PB5-Pad41)") (class "Default")
      (node (ref "U2") (pin "41") (pinfunction "PB5_41") (pintype "bidirectional"))
    )
    (net (code "65") (name "unconnected-(U2-PB6-Pad42)") (class "Default")
      (node (ref "U2") (pin "42") (pinfunction "PB6_42") (pintype "bidirectional"))
    )
    (net (code "66") (name "unconnected-(U2-PB7-Pad43)") (class "Default")
      (node (ref "U2") (pin "43") (pinfunction "PB7_43") (pintype "bidirectional"))
    )
    (net (code "67") (name "unconnected-(U2-PB8-Pad45)") (class "Default")
      (node (ref "U2") (pin "45") (pinfunction "PB8_45") (pintype "bidirectional"))
    )
    (net (code "68") (name "unconnected-(U2-PB9-Pad46)") (class "Default")
      (node (ref "U2") (pin "46") (pinfunction "PB9_46") (pintype "bidirectional"))
    )
    (net (code "69") (name "unconnected-(U2-PB11-Pad22)") (class "Default")
      (node (ref "U2") (pin "22") (pinfunction "PB11_22") (pintype "bidirectional"))
    )
    (net (code "70") (name "unconnected-(U2-PC15-Pad4)") (class "Default")
      (node (ref "U2") (pin "4") (pinfunction "PC15_4") (pintype "bidirectional+no_connect"))
    )
  )
)
